# A4a_STM32.net
KiCad netlist of a schematic drawn in EAGLE
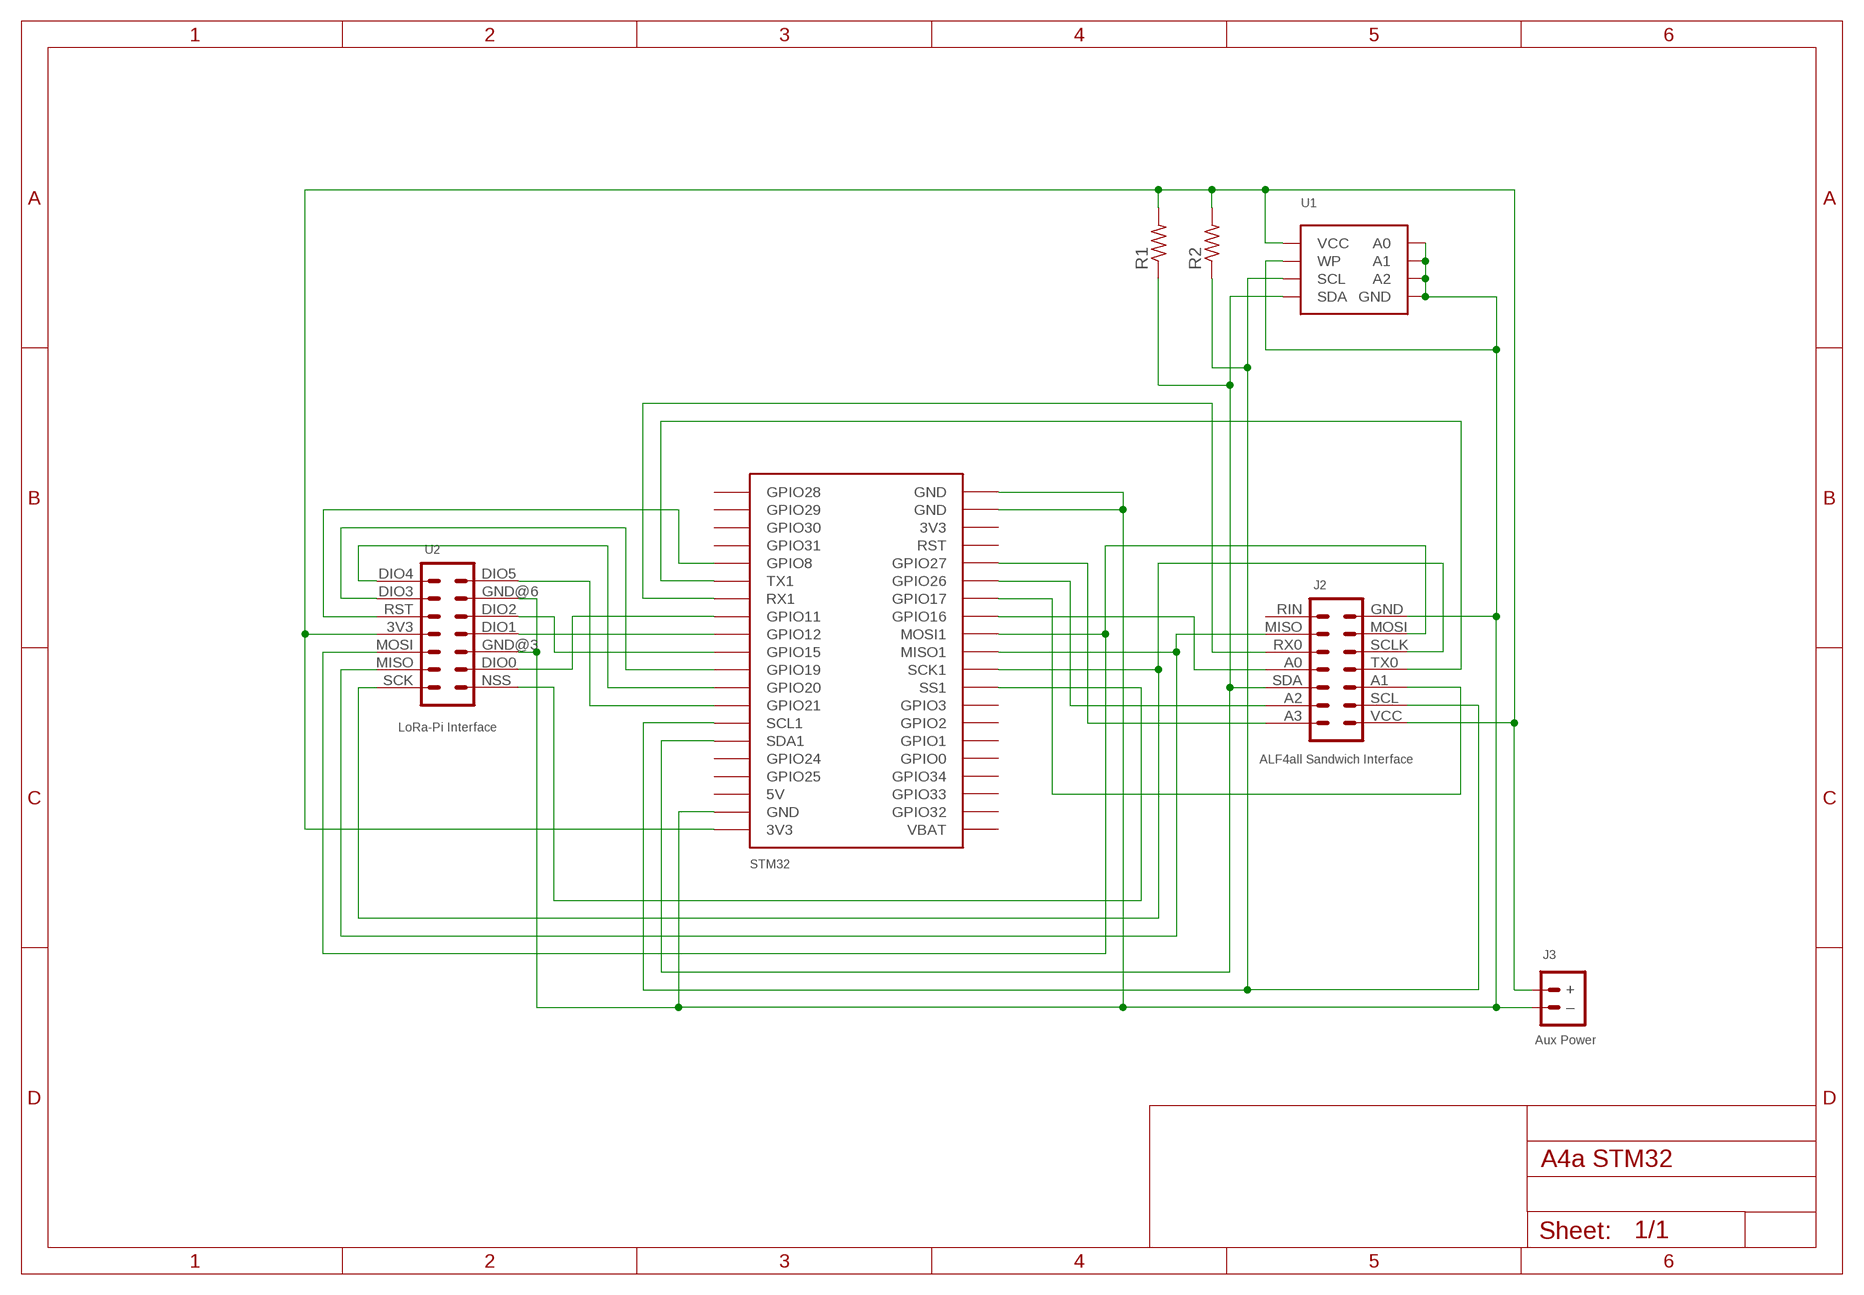
[diagram p0: schematic, sheet 1]

(export (version "E")
  (design (tool "Eeschema 10.0.6"))
  (components
    (comp (ref "J1")
      (value "STM32")
      (footprint "eagle-import:STM32")
      (libsource (lib "eagle-import") (part "STM32"))
    )
    (comp (ref "J2")
      (value "ALF4all Sandwich Interface")
      (footprint "eagle-import:CONN_3X5-ALF4ALL-STM32-INTERCONNECT")
      (libsource (lib "eagle-import") (part "HEADER-3X5-ALF4ALL-STM32-INTERCONNECT"))
    )
    (comp (ref "J3")
      (value "Aux Power")
      (footprint "eagle-import:JST-PH2.0-2-HORIZONTAL")
      (libsource (lib "eagle-import") (part "JST-PH2.0-2-MALE-HORIZONTALJST-PTH-2"))
    )
    (comp (ref "R1")
      (value "RESISTORR0805")
      (footprint "eagle-import:R0805")
      (libsource (lib "eagle-import") (part "RESISTORR0805"))
    )
    (comp (ref "R2")
      (value "RESISTORR0805")
      (footprint "eagle-import:R0805")
      (libsource (lib "eagle-import") (part "RESISTORR0805"))
    )
    (comp (ref "U1")
      (value "AT24CXX-EEPROM-VIA-4")
      (footprint "eagle-import:SOP-8-WITH-VIA-4")
      (libsource (lib "eagle-import") (part "AT24CXX-EEPROM-VIA-4"))
    )
    (comp (ref "U2")
      (value "LoRa-Pi Interface")
      (footprint "eagle-import:RFM95W-PI")
      (libsource (lib "eagle-import") (part "RFM95W-PI-HEADER"))
    )
  )
  (nets
    (net (code "1") (name "Net-(J1-MISO1)") (class "Default")
      (node (ref "J1") (pin "GPIO6") (pinfunction "MISO1_GPIO6") (pintype "bidirectional"))
      (node (ref "J2") (pin "MISO") (pinfunction "9_MISO") (pintype "passive"))
      (node (ref "U2") (pin "MISO") (pinfunction "13_MISO") (pintype "passive"))
    )
    (net (code "2") (name "Net-(J1-MOSI1)") (class "Default")
      (node (ref "J1") (pin "GPIO7") (pinfunction "MOSI1_GPIO7") (pintype "bidirectional"))
      (node (ref "J2") (pin "MOSI") (pinfunction "6_MOSI") (pintype "passive"))
      (node (ref "U2") (pin "MOSI") (pinfunction "12_MOSI") (pintype "passive"))
    )
    (net (code "3") (name "Net-(J1-RX1)") (class "Default")
      (node (ref "J1") (pin "GPIO10") (pinfunction "RX1_GPIO10") (pintype "bidirectional"))
      (node (ref "J2") (pin "RX0") (pinfunction "10_RX0") (pintype "passive"))
    )
    (net (code "4") (name "Net-(J1-SCK1)") (class "Default")
      (node (ref "J1") (pin "GPIO5") (pinfunction "SCK1_GPIO5") (pintype "bidirectional"))
      (node (ref "J2") (pin "SCLK") (pinfunction "5_SCLK") (pintype "passive"))
      (node (ref "U2") (pin "SCK") (pinfunction "14_SCK") (pintype "passive"))
    )
    (net (code "5") (name "Net-(J1-SCL1)") (class "Default")
      (node (ref "J1") (pin "GPIO22") (pinfunction "SCL1_GPIO22") (pintype "bidirectional"))
      (node (ref "J2") (pin "SCL") (pinfunction "2_SCL") (pintype "passive"))
      (node (ref "R2") (pin "1") (pinfunction "1_1") (pintype "passive"))
      (node (ref "U1") (pin "P$6") (pinfunction "SCL_P$6") (pintype "bidirectional"))
    )
    (net (code "6") (name "Net-(J1-SDA1)") (class "Default")
      (node (ref "J1") (pin "GPIO23") (pinfunction "SDA1_GPIO23") (pintype "bidirectional"))
      (node (ref "J2") (pin "SDA") (pinfunction "12_SDA") (pintype "passive"))
      (node (ref "R1") (pin "1") (pinfunction "1_1") (pintype "passive"))
      (node (ref "U1") (pin "P$5") (pinfunction "SDA_P$5") (pintype "bidirectional"))
    )
    (net (code "7") (name "Net-(J1-SS1)") (class "Default")
      (node (ref "J1") (pin "GPIO4") (pinfunction "SS1_GPIO4") (pintype "bidirectional"))
      (node (ref "U2") (pin "NSS") (pinfunction "1_NSS") (pintype "passive"))
    )
    (net (code "8") (name "Net-(J1-TX1)") (class "Default")
      (node (ref "J1") (pin "GPIO9") (pinfunction "TX1_GPIO9") (pintype "bidirectional"))
      (node (ref "J2") (pin "TX0") (pinfunction "4_TX0") (pintype "passive"))
    )
    (net (code "9") (name "Net-(J2-1)") (class "Default")
      (node (ref "J1") (pin "3V3@40") (pinfunction "3V3_3V3@40") (pintype "bidirectional"))
      (node (ref "J2") (pin "VCC") (pinfunction "1_VCC") (pintype "passive"))
      (node (ref "J3") (pin "+") (pinfunction "+_+") (pintype "power_in"))
      (node (ref "R1") (pin "2") (pinfunction "2_2") (pintype "passive"))
      (node (ref "R2") (pin "2") (pinfunction "2_2") (pintype "passive"))
      (node (ref "U1") (pin "P$8") (pinfunction "VCC_P$8") (pintype "bidirectional"))
      (node (ref "U2") (pin "3V3") (pinfunction "11_3V3") (pintype "passive"))
    )
    (net (code "10") (name "Net-(J2-3)") (class "Default")
      (node (ref "J1") (pin "GPIO17") (pinfunction "GPIO17_GPIO17") (pintype "bidirectional"))
      (node (ref "J2") (pin "A1") (pinfunction "3_A1") (pintype "passive"))
    )
    (net (code "11") (name "Net-(J2-7)") (class "Default")
      (node (ref "J1") (pin "GND@19") (pinfunction "GND_GND@19") (pintype "bidirectional"))
      (node (ref "J1") (pin "GND@20") (pinfunction "GND_GND@20") (pintype "bidirectional"))
      (node (ref "J1") (pin "GND@39") (pinfunction "GND_GND@39") (pintype "bidirectional"))
      (node (ref "J2") (pin "GND") (pinfunction "7_GND") (pintype "passive"))
      (node (ref "J3") (pin "-") (pinfunction "–_-") (pintype "power_in"))
      (node (ref "U1") (pin "P$1") (pinfunction "A0_P$1") (pintype "bidirectional"))
      (node (ref "U1") (pin "P$2") (pinfunction "A1_P$2") (pintype "bidirectional"))
      (node (ref "U1") (pin "P$3") (pinfunction "A2_P$3") (pintype "bidirectional"))
      (node (ref "U1") (pin "P$4") (pinfunction "GND_P$4") (pintype "bidirectional"))
      (node (ref "U1") (pin "P$4@VIA") (pinfunction "GND_P$4@VIA") (pintype "bidirectional"))
      (node (ref "U1") (pin "P$7") (pinfunction "WP_P$7") (pintype "bidirectional"))
      (node (ref "U2") (pin "GND@3") (pinfunction "3_GND@3") (pintype "passive"))
      (node (ref "U2") (pin "GND@6") (pinfunction "6_GND@6") (pintype "passive"))
    )
    (net (code "12") (name "Net-(J2-11)") (class "Default")
      (node (ref "J1") (pin "GPIO16") (pinfunction "GPIO16_GPIO16") (pintype "bidirectional"))
      (node (ref "J2") (pin "A0") (pinfunction "11_A0") (pintype "passive"))
    )
    (net (code "13") (name "Net-(J2-13)") (class "Default")
      (node (ref "J1") (pin "GPIO26") (pinfunction "GPIO26_GPIO26") (pintype "bidirectional"))
      (node (ref "J2") (pin "A2") (pinfunction "13_A2") (pintype "passive"))
    )
    (net (code "14") (name "Net-(J2-14)") (class "Default")
      (node (ref "J1") (pin "GPIO27") (pinfunction "GPIO27_GPIO27") (pintype "bidirectional"))
      (node (ref "J2") (pin "A3") (pinfunction "14_A3") (pintype "passive"))
    )
    (net (code "15") (name "Net-(U2-2)") (class "Default")
      (node (ref "J1") (pin "GPIO11") (pinfunction "GPIO11_GPIO11") (pintype "bidirectional"))
      (node (ref "U2") (pin "DIO0") (pinfunction "2_DIO0") (pintype "passive"))
    )
    (net (code "16") (name "Net-(U2-4)") (class "Default")
      (node (ref "J1") (pin "GPIO12") (pinfunction "GPIO12_GPIO12") (pintype "bidirectional"))
      (node (ref "U2") (pin "DIO1") (pinfunction "4_DIO1") (pintype "passive"))
    )
    (net (code "17") (name "Net-(U2-5)") (class "Default")
      (node (ref "J1") (pin "GPIO15") (pinfunction "GPIO15_GPIO15") (pintype "bidirectional"))
      (node (ref "U2") (pin "DIO2") (pinfunction "5_DIO2") (pintype "passive"))
    )
    (net (code "18") (name "Net-(U2-7)") (class "Default")
      (node (ref "J1") (pin "GPIO21") (pinfunction "GPIO21_GPIO21") (pintype "bidirectional"))
      (node (ref "U2") (pin "DIO5") (pinfunction "7_DIO5") (pintype "passive"))
    )
    (net (code "19") (name "Net-(U2-8)") (class "Default")
      (node (ref "J1") (pin "GPIO20") (pinfunction "GPIO20_GPIO20") (pintype "bidirectional"))
      (node (ref "U2") (pin "DIO4") (pinfunction "8_DIO4") (pintype "passive"))
    )
    (net (code "20") (name "Net-(U2-9)") (class "Default")
      (node (ref "J1") (pin "GPIO19") (pinfunction "GPIO19_GPIO19") (pintype "bidirectional"))
      (node (ref "U2") (pin "DIO3") (pinfunction "9_DIO3") (pintype "passive"))
    )
    (net (code "21") (name "Net-(U2-10)") (class "Default")
      (node (ref "J1") (pin "GPIO8") (pinfunction "GPIO8_GPIO8") (pintype "bidirectional"))
      (node (ref "U2") (pin "RST") (pinfunction "10_RST") (pintype "passive"))
    )
    (net (code "22") (name "unconnected-(J1-3V3-Pad3V3@18)") (class "Default")
      (node (ref "J1") (pin "3V3@18") (pinfunction "3V3_3V3@18") (pintype "bidirectional"))
    )
    (net (code "23") (name "unconnected-(J1-5V-Pad5V@38)") (class "Default")
      (node (ref "J1") (pin "5V@38") (pinfunction "5V_5V@38") (pintype "bidirectional"))
    )
    (net (code "24") (name "unconnected-(J1-PadGPIO0)") (class "Default")
      (node (ref "J1") (pin "GPIO0") (pinfunction "GPIO0_GPIO0") (pintype "bidirectional"))
    )
    (net (code "25") (name "unconnected-(J1-PadGPIO1)") (class "Default")
      (node (ref "J1") (pin "GPIO1") (pinfunction "GPIO1_GPIO1") (pintype "bidirectional"))
    )
    (net (code "26") (name "unconnected-(J1-PadGPIO2)") (class "Default")
      (node (ref "J1") (pin "GPIO2") (pinfunction "GPIO2_GPIO2") (pintype "bidirectional"))
    )
    (net (code "27") (name "unconnected-(J1-PadGPIO3)") (class "Default")
      (node (ref "J1") (pin "GPIO3") (pinfunction "GPIO3_GPIO3") (pintype "bidirectional"))
    )
    (net (code "28") (name "unconnected-(J1-PadGPIO24)") (class "Default")
      (node (ref "J1") (pin "GPIO24") (pinfunction "GPIO24_GPIO24") (pintype "bidirectional"))
    )
    (net (code "29") (name "unconnected-(J1-PadGPIO25)") (class "Default")
      (node (ref "J1") (pin "GPIO25") (pinfunction "GPIO25_GPIO25") (pintype "bidirectional"))
    )
    (net (code "30") (name "unconnected-(J1-PadGPIO28)") (class "Default")
      (node (ref "J1") (pin "GPIO28") (pinfunction "GPIO28_GPIO28") (pintype "bidirectional"))
    )
    (net (code "31") (name "unconnected-(J1-PadGPIO29)") (class "Default")
      (node (ref "J1") (pin "GPIO29") (pinfunction "GPIO29_GPIO29") (pintype "bidirectional"))
    )
    (net (code "32") (name "unconnected-(J1-PadGPIO30)") (class "Default")
      (node (ref "J1") (pin "GPIO30") (pinfunction "GPIO30_GPIO30") (pintype "bidirectional"))
    )
    (net (code "33") (name "unconnected-(J1-PadGPIO31)") (class "Default")
      (node (ref "J1") (pin "GPIO31") (pinfunction "GPIO31_GPIO31") (pintype "bidirectional"))
    )
    (net (code "34") (name "unconnected-(J1-PadGPIO32)") (class "Default")
      (node (ref "J1") (pin "GPIO32") (pinfunction "GPIO32_GPIO32") (pintype "bidirectional"))
    )
    (net (code "35") (name "unconnected-(J1-PadGPIO33)") (class "Default")
      (node (ref "J1") (pin "GPIO33") (pinfunction "GPIO33_GPIO33") (pintype "bidirectional"))
    )
    (net (code "36") (name "unconnected-(J1-PadGPIO34)") (class "Default")
      (node (ref "J1") (pin "GPIO34") (pinfunction "GPIO34_GPIO34") (pintype "bidirectional"))
    )
    (net (code "37") (name "unconnected-(J1-PadRST)") (class "Default")
      (node (ref "J1") (pin "RST") (pinfunction "RST_RST") (pintype "bidirectional"))
    )
    (net (code "38") (name "unconnected-(J1-PadVBAT)") (class "Default")
      (node (ref "J1") (pin "VBAT") (pinfunction "VBAT_VBAT") (pintype "bidirectional"))
    )
    (net (code "39") (name "unconnected-(J2-8-PadRIN)") (class "Default")
      (node (ref "J2") (pin "RIN") (pinfunction "8_RIN") (pintype "passive"))
    )
  )
)
